# countercat_current.net
KiCad netlist of a schematic drawn in EAGLE
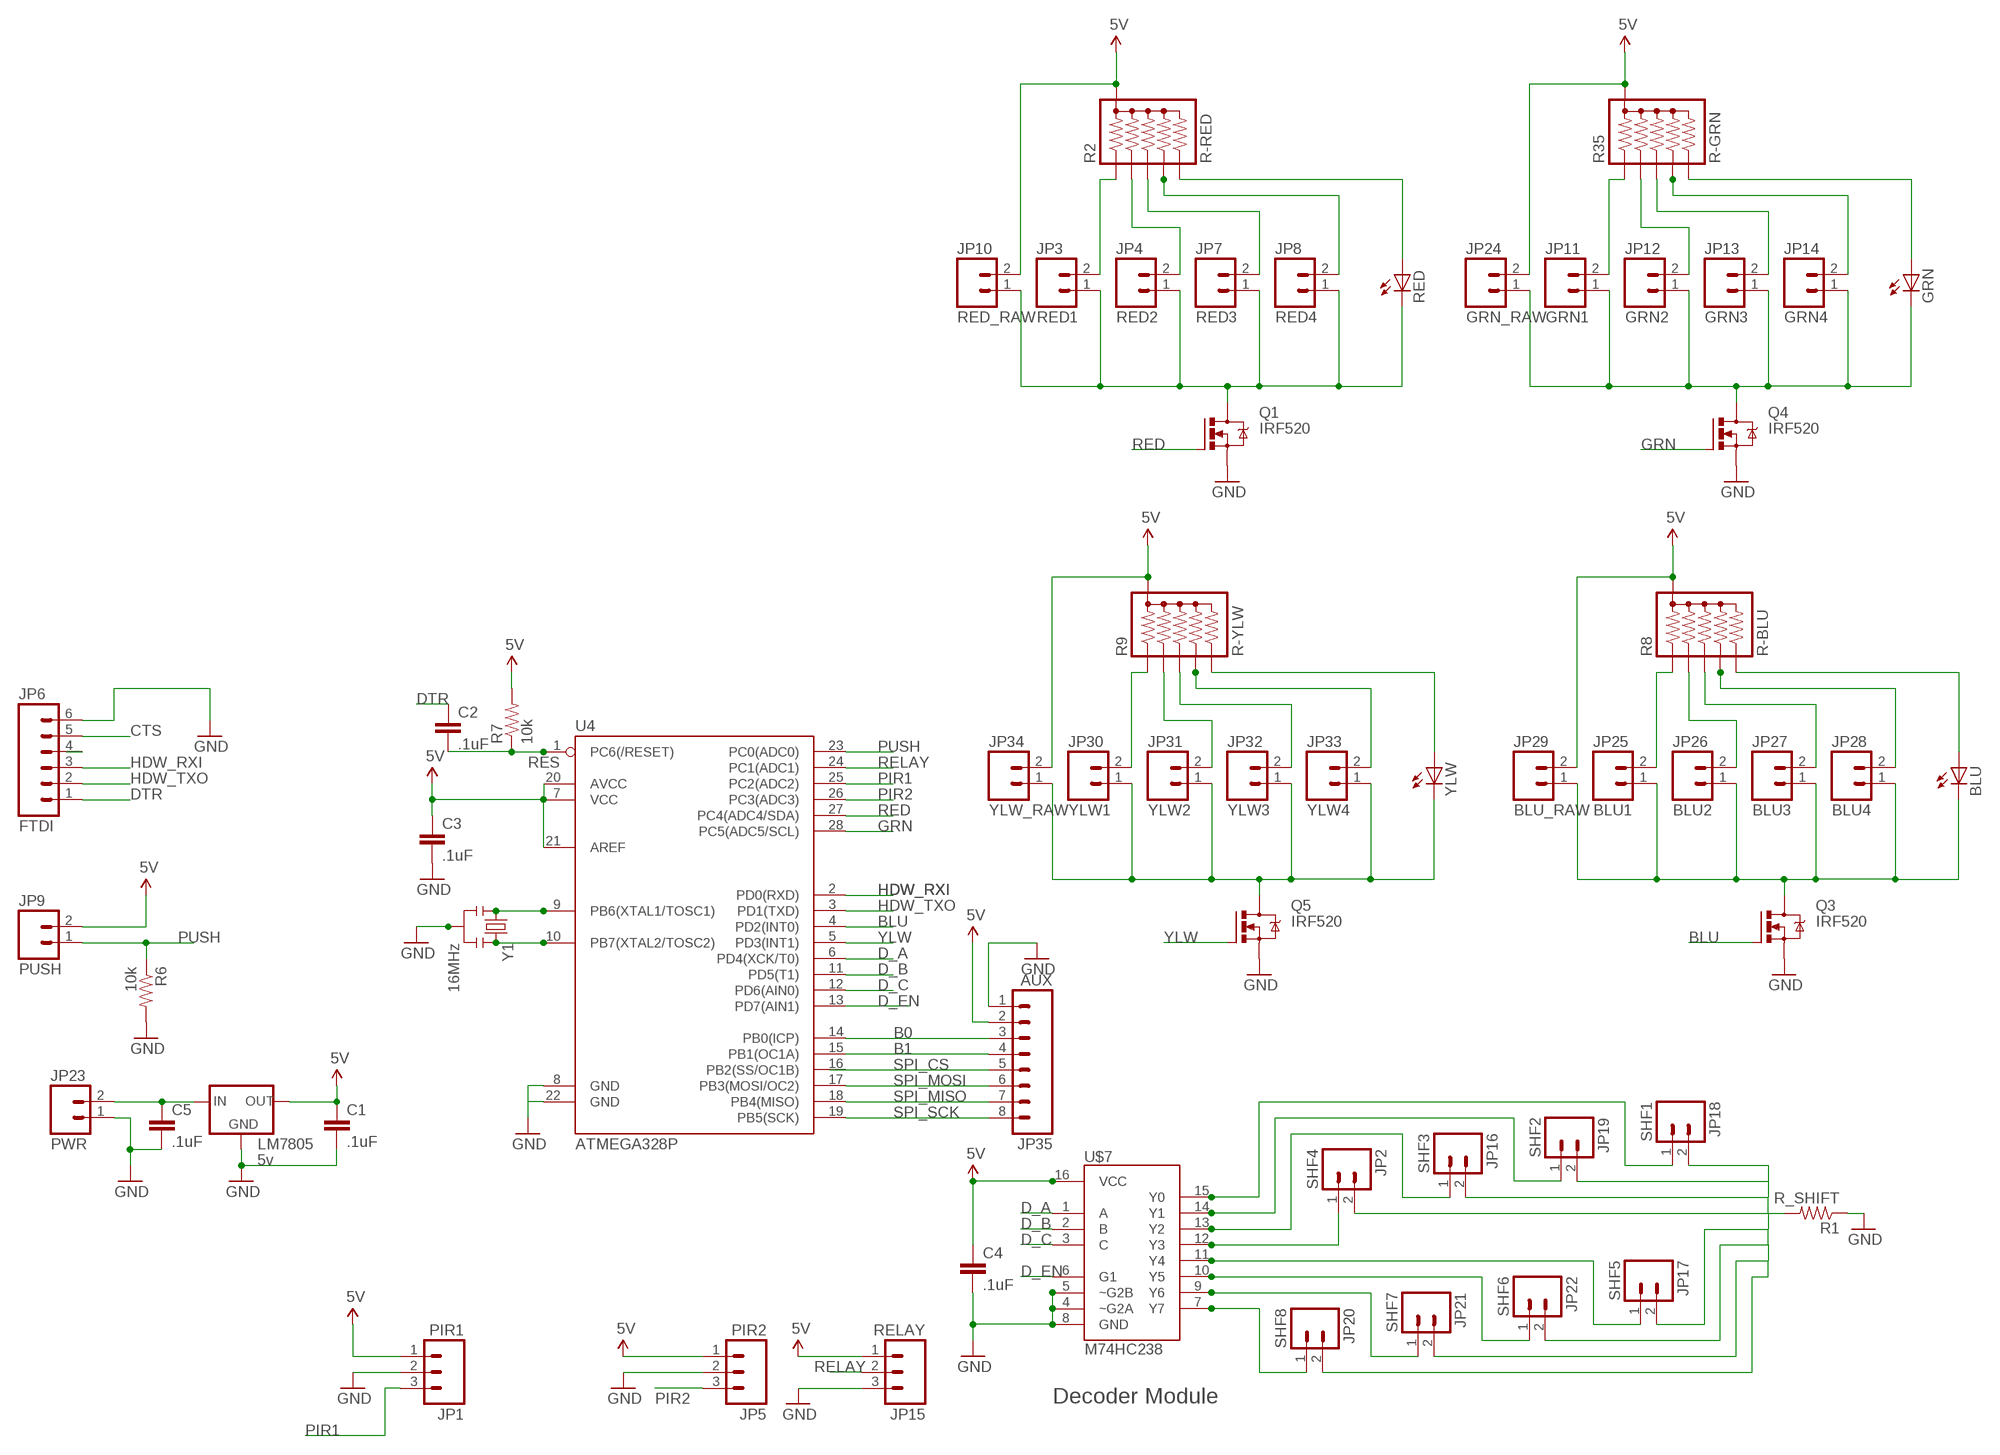
[diagram p0: schematic, sheet 1]

(export (version "E")
  (design (tool "Eeschema 10.0.6"))
  (components
    (comp (ref "BLU")
      (value "LED3MM")
      (footprint "eagle-import:LED3MM")
      (libsource (lib "eagle-import") (part "LED3MM"))
    )
    (comp (ref "C1")
      (value ".1uF")
      (footprint "eagle-import:CAP-PTH-SMALL2")
      (libsource (lib "eagle-import") (part "CAPPTH2"))
    )
    (comp (ref "C2")
      (value ".1uF")
      (footprint "eagle-import:CAP-PTH-SMALL2")
      (libsource (lib "eagle-import") (part "CAPPTH2"))
    )
    (comp (ref "C3")
      (value ".1uF")
      (footprint "eagle-import:CAP-PTH-SMALL2")
      (libsource (lib "eagle-import") (part "CAPPTH2"))
    )
    (comp (ref "C4")
      (value ".1uF")
      (footprint "eagle-import:CAP-PTH-SMALL2")
      (libsource (lib "eagle-import") (part "CAPPTH2"))
    )
    (comp (ref "C5")
      (value ".1uF")
      (footprint "eagle-import:CAP-PTH-SMALL2")
      (libsource (lib "eagle-import") (part "CAPPTH2"))
    )
    (comp (ref "GRN")
      (value "LED3MM")
      (footprint "eagle-import:LED3MM")
      (libsource (lib "eagle-import") (part "LED3MM"))
    )
    (comp (ref "JP1")
      (value "PIR1")
      (footprint "eagle-import:MOLEX-1X3")
      (libsource (lib "eagle-import") (part "M03POLAR"))
    )
    (comp (ref "JP2")
      (value "SHF4")
      (footprint "eagle-import:MOLEX-1X2")
      (libsource (lib "eagle-import") (part "M02POLAR"))
    )
    (comp (ref "JP3")
      (value "RED1")
      (footprint "eagle-import:MOLEX-1X2")
      (libsource (lib "eagle-import") (part "M02POLAR"))
    )
    (comp (ref "JP4")
      (value "RED2")
      (footprint "eagle-import:MOLEX-1X2")
      (libsource (lib "eagle-import") (part "M02POLAR"))
    )
    (comp (ref "JP5")
      (value "PIR2")
      (footprint "eagle-import:MOLEX-1X3")
      (libsource (lib "eagle-import") (part "M03POLAR"))
    )
    (comp (ref "JP6")
      (value "FTDI")
      (footprint "eagle-import:1X06_LOCK")
      (libsource (lib "eagle-import") (part "M06LOCK"))
    )
    (comp (ref "JP7")
      (value "RED3")
      (footprint "eagle-import:MOLEX-1X2")
      (libsource (lib "eagle-import") (part "M02POLAR"))
    )
    (comp (ref "JP8")
      (value "RED4")
      (footprint "eagle-import:MOLEX-1X2")
      (libsource (lib "eagle-import") (part "M02POLAR"))
    )
    (comp (ref "JP9")
      (value "PUSH")
      (footprint "eagle-import:MOLEX-1X2")
      (libsource (lib "eagle-import") (part "M02POLAR"))
    )
    (comp (ref "JP10")
      (value "RED_RAW")
      (footprint "eagle-import:MOLEX-1X2")
      (libsource (lib "eagle-import") (part "M02POLAR"))
    )
    (comp (ref "JP11")
      (value "GRN1")
      (footprint "eagle-import:MOLEX-1X2")
      (libsource (lib "eagle-import") (part "M02POLAR"))
    )
    (comp (ref "JP12")
      (value "GRN2")
      (footprint "eagle-import:MOLEX-1X2")
      (libsource (lib "eagle-import") (part "M02POLAR"))
    )
    (comp (ref "JP13")
      (value "GRN3")
      (footprint "eagle-import:MOLEX-1X2")
      (libsource (lib "eagle-import") (part "M02POLAR"))
    )
    (comp (ref "JP14")
      (value "GRN4")
      (footprint "eagle-import:MOLEX-1X2")
      (libsource (lib "eagle-import") (part "M02POLAR"))
    )
    (comp (ref "JP15")
      (value "RELAY")
      (footprint "eagle-import:MOLEX-1X3")
      (libsource (lib "eagle-import") (part "M03POLAR"))
    )
    (comp (ref "JP16")
      (value "SHF3")
      (footprint "eagle-import:MOLEX-1X2")
      (libsource (lib "eagle-import") (part "M02POLAR"))
    )
    (comp (ref "JP17")
      (value "SHF5")
      (footprint "eagle-import:MOLEX-1X2")
      (libsource (lib "eagle-import") (part "M02POLAR"))
    )
    (comp (ref "JP18")
      (value "SHF1")
      (footprint "eagle-import:MOLEX-1X2")
      (libsource (lib "eagle-import") (part "M02POLAR"))
    )
    (comp (ref "JP19")
      (value "SHF2")
      (footprint "eagle-import:MOLEX-1X2")
      (libsource (lib "eagle-import") (part "M02POLAR"))
    )
    (comp (ref "JP20")
      (value "SHF8")
      (footprint "eagle-import:MOLEX-1X2")
      (libsource (lib "eagle-import") (part "M02POLAR"))
    )
    (comp (ref "JP21")
      (value "SHF7")
      (footprint "eagle-import:MOLEX-1X2")
      (libsource (lib "eagle-import") (part "M02POLAR"))
    )
    (comp (ref "JP22")
      (value "SHF6")
      (footprint "eagle-import:MOLEX-1X2")
      (libsource (lib "eagle-import") (part "M02POLAR"))
    )
    (comp (ref "JP23")
      (value "PWR")
      (footprint "eagle-import:MOLEX-1X2")
      (libsource (lib "eagle-import") (part "M02POLAR"))
    )
    (comp (ref "JP24")
      (value "GRN_RAW")
      (footprint "eagle-import:MOLEX-1X2")
      (libsource (lib "eagle-import") (part "M02POLAR"))
    )
    (comp (ref "JP25")
      (value "BLU1")
      (footprint "eagle-import:MOLEX-1X2")
      (libsource (lib "eagle-import") (part "M02POLAR"))
    )
    (comp (ref "JP26")
      (value "BLU2")
      (footprint "eagle-import:MOLEX-1X2")
      (libsource (lib "eagle-import") (part "M02POLAR"))
    )
    (comp (ref "JP27")
      (value "BLU3")
      (footprint "eagle-import:MOLEX-1X2")
      (libsource (lib "eagle-import") (part "M02POLAR"))
    )
    (comp (ref "JP28")
      (value "BLU4")
      (footprint "eagle-import:MOLEX-1X2")
      (libsource (lib "eagle-import") (part "M02POLAR"))
    )
    (comp (ref "JP29")
      (value "BLU_RAW")
      (footprint "eagle-import:MOLEX-1X2")
      (libsource (lib "eagle-import") (part "M02POLAR"))
    )
    (comp (ref "JP30")
      (value "YLW1")
      (footprint "eagle-import:MOLEX-1X2")
      (libsource (lib "eagle-import") (part "M02POLAR"))
    )
    (comp (ref "JP31")
      (value "YLW2")
      (footprint "eagle-import:MOLEX-1X2")
      (libsource (lib "eagle-import") (part "M02POLAR"))
    )
    (comp (ref "JP32")
      (value "YLW3")
      (footprint "eagle-import:MOLEX-1X2")
      (libsource (lib "eagle-import") (part "M02POLAR"))
    )
    (comp (ref "JP33")
      (value "YLW4")
      (footprint "eagle-import:MOLEX-1X2")
      (libsource (lib "eagle-import") (part "M02POLAR"))
    )
    (comp (ref "JP34")
      (value "YLW_RAW")
      (footprint "eagle-import:MOLEX-1X2")
      (libsource (lib "eagle-import") (part "M02POLAR"))
    )
    (comp (ref "JP35")
      (value "AUX")
      (footprint "eagle-import:1X08_LOCK")
      (libsource (lib "eagle-import") (part "M08LOCK"))
    )
    (comp (ref "LM7805")
      (value "5v")
      (footprint "eagle-import:TO220-IGO")
      (libsource (lib "eagle-import") (part "V_REG_78XXSINK"))
    )
    (comp (ref "Q1")
      (value "IRF520")
      (footprint "eagle-import:TO220BV")
      (libsource (lib "eagle-import") (part "IRF520"))
    )
    (comp (ref "Q3")
      (value "IRF520")
      (footprint "eagle-import:TO220BV")
      (libsource (lib "eagle-import") (part "IRF520"))
    )
    (comp (ref "Q4")
      (value "IRF520")
      (footprint "eagle-import:TO220BV")
      (libsource (lib "eagle-import") (part "IRF520"))
    )
    (comp (ref "Q5")
      (value "IRF520")
      (footprint "eagle-import:TO220BV")
      (libsource (lib "eagle-import") (part "IRF520"))
    )
    (comp (ref "R1")
      (value "R_SHIFT")
      (footprint "eagle-import:AXIAL-0.4")
      (libsource (lib "eagle-import") (part "RESISTORPTH-1/4W"))
    )
    (comp (ref "R2")
      (value "R-RED")
      (footprint "eagle-import:RPACK-SIP-PTH-5")
      (libsource (lib "eagle-import") (part "RPACK-BUSSED-5-SIP-PTH-5"))
    )
    (comp (ref "R6")
      (value "10k")
      (footprint "eagle-import:AXIAL-0.4")
      (libsource (lib "eagle-import") (part "RESISTORPTH-1/4W"))
    )
    (comp (ref "R7")
      (value "10k")
      (footprint "eagle-import:AXIAL-0.4")
      (libsource (lib "eagle-import") (part "RESISTORPTH-1/4W"))
    )
    (comp (ref "R8")
      (value "R-BLU")
      (footprint "eagle-import:RPACK-SIP-PTH-5")
      (libsource (lib "eagle-import") (part "RPACK-BUSSED-5-SIP-PTH-5"))
    )
    (comp (ref "R9")
      (value "R-YLW")
      (footprint "eagle-import:RPACK-SIP-PTH-5")
      (libsource (lib "eagle-import") (part "RPACK-BUSSED-5-SIP-PTH-5"))
    )
    (comp (ref "R35")
      (value "R-GRN")
      (footprint "eagle-import:RPACK-SIP-PTH-5")
      (libsource (lib "eagle-import") (part "RPACK-BUSSED-5-SIP-PTH-5"))
    )
    (comp (ref "RED")
      (value "LED3MM")
      (footprint "eagle-import:LED3MM")
      (libsource (lib "eagle-import") (part "LED3MM"))
    )
    (comp (ref "U$7")
      (value "M74HC238")
      (footprint "eagle-import:DIL16")
      (libsource (lib "eagle-import") (part "M74HC238"))
    )
    (comp (ref "U4")
      (value "ATMEGA328P")
      (footprint "eagle-import:DIL28-3")
      (libsource (lib "eagle-import") (part "ATMEGA328P_PDIP"))
    )
    (comp (ref "Y1")
      (value "16MHz")
      (footprint "eagle-import:RESONATOR-PTH")
      (libsource (lib "eagle-import") (part "RESONATORPTH"))
    )
    (comp (ref "YLW")
      (value "LED3MM")
      (footprint "eagle-import:LED3MM")
      (libsource (lib "eagle-import") (part "LED3MM"))
    )
  )
  (nets
    (net (code "1") (name "/B0") (class "Default")
      (node (ref "JP35") (pin "3") (pinfunction "3_3") (pintype "passive"))
      (node (ref "U4") (pin "14") (pinfunction "PB0(ICP)_14") (pintype "bidirectional"))
    )
    (net (code "2") (name "/B1") (class "Default")
      (node (ref "JP35") (pin "4") (pinfunction "4_4") (pintype "passive"))
      (node (ref "U4") (pin "15") (pinfunction "PB1(OC1A)_15") (pintype "bidirectional"))
    )
    (net (code "3") (name "/BLU") (class "Default")
      (node (ref "Q3") (pin "G") (pinfunction "G_G") (pintype "passive"))
      (node (ref "U4") (pin "4") (pinfunction "PD2(INT0)_4") (pintype "bidirectional"))
    )
    (net (code "4") (name "/CTS") (class "Default")
      (node (ref "JP6") (pin "5") (pinfunction "5_5") (pintype "passive"))
    )
    (net (code "5") (name "/DTR") (class "Default")
      (node (ref "C2") (pin "1") (pinfunction "1_1") (pintype "passive"))
      (node (ref "JP6") (pin "1") (pinfunction "1_1") (pintype "passive"))
    )
    (net (code "6") (name "/D_A") (class "Default")
      (node (ref "U$7") (pin "1") (pinfunction "A_1") (pintype "bidirectional"))
      (node (ref "U4") (pin "6") (pinfunction "PD4(XCK/T0)_6") (pintype "bidirectional"))
    )
    (net (code "7") (name "/D_B") (class "Default")
      (node (ref "U$7") (pin "2") (pinfunction "B_2") (pintype "bidirectional"))
      (node (ref "U4") (pin "11") (pinfunction "PD5(T1)_11") (pintype "bidirectional"))
    )
    (net (code "8") (name "/D_C") (class "Default")
      (node (ref "U$7") (pin "3") (pinfunction "C_3") (pintype "bidirectional"))
      (node (ref "U4") (pin "12") (pinfunction "PD6(AIN0)_12") (pintype "bidirectional"))
    )
    (net (code "9") (name "/D_EN") (class "Default")
      (node (ref "U$7") (pin "6") (pinfunction "G1_6") (pintype "bidirectional"))
      (node (ref "U4") (pin "13") (pinfunction "PD7(AIN1)_13") (pintype "bidirectional"))
    )
    (net (code "10") (name "/GRN") (class "Default")
      (node (ref "Q4") (pin "G") (pinfunction "G_G") (pintype "passive"))
      (node (ref "U4") (pin "28") (pinfunction "PC5(ADC5/SCL)_28") (pintype "bidirectional"))
    )
    (net (code "11") (name "/HDW_RXI") (class "Default")
      (node (ref "JP6") (pin "3") (pinfunction "3_3") (pintype "passive"))
      (node (ref "U4") (pin "2") (pinfunction "PD0(RXD)_2") (pintype "bidirectional"))
    )
    (net (code "12") (name "/HDW_TXO") (class "Default")
      (node (ref "JP6") (pin "2") (pinfunction "2_2") (pintype "passive"))
      (node (ref "U4") (pin "3") (pinfunction "PD1(TXD)_3") (pintype "bidirectional"))
    )
    (net (code "13") (name "/PIR1") (class "Default")
      (node (ref "JP1") (pin "3") (pinfunction "3_3") (pintype "passive"))
      (node (ref "U4") (pin "25") (pinfunction "PC2(ADC2)_25") (pintype "bidirectional"))
    )
    (net (code "14") (name "/PIR2") (class "Default")
      (node (ref "JP5") (pin "3") (pinfunction "3_3") (pintype "passive"))
      (node (ref "U4") (pin "26") (pinfunction "PC3(ADC3)_26") (pintype "bidirectional"))
    )
    (net (code "15") (name "/PUSH") (class "Default")
      (node (ref "JP9") (pin "1") (pinfunction "1_1") (pintype "passive"))
      (node (ref "R6") (pin "P$1") (pinfunction "1_P$1") (pintype "passive"))
      (node (ref "U4") (pin "23") (pinfunction "PC0(ADC0)_23") (pintype "bidirectional"))
    )
    (net (code "16") (name "/RED") (class "Default")
      (node (ref "Q1") (pin "G") (pinfunction "G_G") (pintype "passive"))
      (node (ref "U4") (pin "27") (pinfunction "PC4(ADC4/SDA)_27") (pintype "bidirectional"))
    )
    (net (code "17") (name "/RELAY") (class "Default")
      (node (ref "JP15") (pin "2") (pinfunction "2_2") (pintype "passive"))
      (node (ref "U4") (pin "24") (pinfunction "PC1(ADC1)_24") (pintype "bidirectional"))
    )
    (net (code "18") (name "/RES") (class "Default")
      (node (ref "C2") (pin "2") (pinfunction "2_2") (pintype "passive"))
      (node (ref "R7") (pin "P$1") (pinfunction "1_P$1") (pintype "passive"))
      (node (ref "U4") (pin "1") (pinfunction "PC6(/RESET)_1") (pintype "bidirectional"))
    )
    (net (code "19") (name "/SPI_CS") (class "Default")
      (node (ref "JP35") (pin "5") (pinfunction "5_5") (pintype "passive"))
      (node (ref "U4") (pin "16") (pinfunction "PB2(SS/OC1B)_16") (pintype "bidirectional"))
    )
    (net (code "20") (name "/SPI_MISO") (class "Default")
      (node (ref "JP35") (pin "7") (pinfunction "7_7") (pintype "passive"))
      (node (ref "U4") (pin "18") (pinfunction "PB4(MISO)_18") (pintype "bidirectional"))
    )
    (net (code "21") (name "/SPI_MOSI") (class "Default")
      (node (ref "JP35") (pin "6") (pinfunction "6_6") (pintype "passive"))
      (node (ref "U4") (pin "17") (pinfunction "PB3(MOSI/OC2)_17") (pintype "bidirectional"))
    )
    (net (code "22") (name "/SPI_SCK") (class "Default")
      (node (ref "JP35") (pin "8") (pinfunction "8_8") (pintype "passive"))
      (node (ref "U4") (pin "19") (pinfunction "PB5(SCK)_19") (pintype "bidirectional"))
    )
    (net (code "23") (name "/YLW") (class "Default")
      (node (ref "Q5") (pin "G") (pinfunction "G_G") (pintype "passive"))
      (node (ref "U4") (pin "5") (pinfunction "PD3(INT1)_5") (pintype "bidirectional"))
    )
    (net (code "24") (name "5V") (class "Default")
      (node (ref "C1") (pin "1") (pinfunction "1_1") (pintype "passive"))
      (node (ref "C3") (pin "1") (pinfunction "1_1") (pintype "passive"))
      (node (ref "C4") (pin "1") (pinfunction "1_1") (pintype "passive"))
      (node (ref "JP1") (pin "1") (pinfunction "1_1") (pintype "passive"))
      (node (ref "JP10") (pin "2") (pinfunction "2_2") (pintype "passive"))
      (node (ref "JP15") (pin "1") (pinfunction "1_1") (pintype "passive"))
      (node (ref "JP24") (pin "2") (pinfunction "2_2") (pintype "passive"))
      (node (ref "JP29") (pin "2") (pinfunction "2_2") (pintype "passive"))
      (node (ref "JP34") (pin "2") (pinfunction "2_2") (pintype "passive"))
      (node (ref "JP35") (pin "2") (pinfunction "2_2") (pintype "passive"))
      (node (ref "JP5") (pin "1") (pinfunction "1_1") (pintype "passive"))
      (node (ref "JP9") (pin "2") (pinfunction "2_2") (pintype "passive"))
      (node (ref "LM7805") (pin "OUT") (pinfunction "OUT_OUT") (pintype "output"))
      (node (ref "R2") (pin "P$1") (pinfunction "1_P$1") (pintype "passive"))
      (node (ref "R35") (pin "P$1") (pinfunction "1_P$1") (pintype "passive"))
      (node (ref "R7") (pin "P$2") (pinfunction "2_P$2") (pintype "passive"))
      (node (ref "R8") (pin "P$1") (pinfunction "1_P$1") (pintype "passive"))
      (node (ref "R9") (pin "P$1") (pinfunction "1_P$1") (pintype "passive"))
      (node (ref "U$7") (pin "16") (pinfunction "VCC_16") (pintype "bidirectional"))
      (node (ref "U4") (pin "20") (pinfunction "AVCC_20") (pintype "bidirectional"))
      (node (ref "U4") (pin "21") (pinfunction "AREF_21") (pintype "bidirectional"))
      (node (ref "U4") (pin "7") (pinfunction "VCC_7") (pintype "bidirectional"))
    )
    (net (code "25") (name "GND") (class "Default")
      (node (ref "C1") (pin "2") (pinfunction "2_2") (pintype "passive"))
      (node (ref "C3") (pin "2") (pinfunction "2_2") (pintype "passive"))
      (node (ref "C4") (pin "2") (pinfunction "2_2") (pintype "passive"))
      (node (ref "C5") (pin "2") (pinfunction "2_2") (pintype "passive"))
      (node (ref "JP1") (pin "2") (pinfunction "2_2") (pintype "passive"))
      (node (ref "JP15") (pin "3") (pinfunction "3_3") (pintype "passive"))
      (node (ref "JP23") (pin "1") (pinfunction "1_1") (pintype "passive"))
      (node (ref "JP35") (pin "1") (pinfunction "1_1") (pintype "passive"))
      (node (ref "JP5") (pin "2") (pinfunction "2_2") (pintype "passive"))
      (node (ref "JP6") (pin "6") (pinfunction "6_6") (pintype "passive"))
      (node (ref "LM7805") (pin "GND") (pinfunction "GND_GND") (pintype "input"))
      (node (ref "Q1") (pin "S") (pinfunction "S_S") (pintype "passive"))
      (node (ref "Q3") (pin "S") (pinfunction "S_S") (pintype "passive"))
      (node (ref "Q4") (pin "S") (pinfunction "S_S") (pintype "passive"))
      (node (ref "Q5") (pin "S") (pinfunction "S_S") (pintype "passive"))
      (node (ref "R1") (pin "P$1") (pinfunction "1_P$1") (pintype "passive"))
      (node (ref "R6") (pin "P$2") (pinfunction "2_P$2") (pintype "passive"))
      (node (ref "U$7") (pin "4") (pinfunction "~{G2A}_4") (pintype "bidirectional"))
      (node (ref "U$7") (pin "5") (pinfunction "~{G2B}_5") (pintype "bidirectional"))
      (node (ref "U$7") (pin "8") (pinfunction "GND_8") (pintype "bidirectional"))
      (node (ref "U4") (pin "22") (pinfunction "GND_22") (pintype "bidirectional"))
      (node (ref "U4") (pin "8") (pinfunction "GND_8") (pintype "bidirectional"))
      (node (ref "Y1") (pin "2") (pinfunction "2_2") (pintype "passive"))
    )
    (net (code "26") (name "Net-(BLU-C)") (class "Default")
      (node (ref "BLU") (pin "K") (pinfunction "C_K") (pintype "passive"))
      (node (ref "JP25") (pin "1") (pinfunction "1_1") (pintype "passive"))
      (node (ref "JP26") (pin "1") (pinfunction "1_1") (pintype "passive"))
      (node (ref "JP27") (pin "1") (pinfunction "1_1") (pintype "passive"))
      (node (ref "JP28") (pin "1") (pinfunction "1_1") (pintype "passive"))
      (node (ref "JP29") (pin "1") (pinfunction "1_1") (pintype "passive"))
      (node (ref "Q3") (pin "D") (pinfunction "D_D") (pintype "passive"))
    )
    (net (code "27") (name "Net-(C5-Pad1)") (class "Default")
      (node (ref "C5") (pin "1") (pinfunction "1_1") (pintype "passive"))
      (node (ref "JP23") (pin "2") (pinfunction "2_2") (pintype "passive"))
      (node (ref "LM7805") (pin "IN") (pinfunction "IN_IN") (pintype "input"))
    )
    (net (code "28") (name "Net-(GRN-C)") (class "Default")
      (node (ref "GRN") (pin "K") (pinfunction "C_K") (pintype "passive"))
      (node (ref "JP11") (pin "1") (pinfunction "1_1") (pintype "passive"))
      (node (ref "JP12") (pin "1") (pinfunction "1_1") (pintype "passive"))
      (node (ref "JP13") (pin "1") (pinfunction "1_1") (pintype "passive"))
      (node (ref "JP14") (pin "1") (pinfunction "1_1") (pintype "passive"))
      (node (ref "JP24") (pin "1") (pinfunction "1_1") (pintype "passive"))
      (node (ref "Q4") (pin "D") (pinfunction "D_D") (pintype "passive"))
    )
    (net (code "29") (name "Net-(R1-2)") (class "Default")
      (node (ref "JP16") (pin "2") (pinfunction "2_2") (pintype "passive"))
      (node (ref "JP17") (pin "2") (pinfunction "2_2") (pintype "passive"))
      (node (ref "JP18") (pin "2") (pinfunction "2_2") (pintype "passive"))
      (node (ref "JP19") (pin "2") (pinfunction "2_2") (pintype "passive"))
      (node (ref "JP2") (pin "2") (pinfunction "2_2") (pintype "passive"))
      (node (ref "JP20") (pin "2") (pinfunction "2_2") (pintype "passive"))
      (node (ref "JP21") (pin "2") (pinfunction "2_2") (pintype "passive"))
      (node (ref "JP22") (pin "2") (pinfunction "2_2") (pintype "passive"))
      (node (ref "R1") (pin "P$2") (pinfunction "2_P$2") (pintype "passive"))
    )
    (net (code "30") (name "Net-(R2-2)") (class "Default")
      (node (ref "JP3") (pin "2") (pinfunction "2_2") (pintype "passive"))
      (node (ref "R2") (pin "P$2") (pinfunction "2_P$2") (pintype "passive"))
    )
    (net (code "31") (name "Net-(R2-3)") (class "Default")
      (node (ref "JP4") (pin "2") (pinfunction "2_2") (pintype "passive"))
      (node (ref "R2") (pin "P$3") (pinfunction "3_P$3") (pintype "passive"))
    )
    (net (code "32") (name "Net-(R2-4)") (class "Default")
      (node (ref "JP7") (pin "2") (pinfunction "2_2") (pintype "passive"))
      (node (ref "R2") (pin "P$4") (pinfunction "4_P$4") (pintype "passive"))
    )
    (net (code "33") (name "Net-(R2-5)") (class "Default")
      (node (ref "JP8") (pin "2") (pinfunction "2_2") (pintype "passive"))
      (node (ref "R2") (pin "P$5") (pinfunction "5_P$5") (pintype "passive"))
    )
    (net (code "34") (name "Net-(R2-6)") (class "Default")
      (node (ref "R2") (pin "P$6") (pinfunction "6_P$6") (pintype "passive"))
      (node (ref "RED") (pin "A") (pinfunction "A_A") (pintype "passive"))
    )
    (net (code "35") (name "Net-(R8-2)") (class "Default")
      (node (ref "JP25") (pin "2") (pinfunction "2_2") (pintype "passive"))
      (node (ref "R8") (pin "P$2") (pinfunction "2_P$2") (pintype "passive"))
    )
    (net (code "36") (name "Net-(R8-3)") (class "Default")
      (node (ref "JP26") (pin "2") (pinfunction "2_2") (pintype "passive"))
      (node (ref "R8") (pin "P$3") (pinfunction "3_P$3") (pintype "passive"))
    )
    (net (code "37") (name "Net-(R8-4)") (class "Default")
      (node (ref "JP27") (pin "2") (pinfunction "2_2") (pintype "passive"))
      (node (ref "R8") (pin "P$4") (pinfunction "4_P$4") (pintype "passive"))
    )
    (net (code "38") (name "Net-(R8-5)") (class "Default")
      (node (ref "JP28") (pin "2") (pinfunction "2_2") (pintype "passive"))
      (node (ref "R8") (pin "P$5") (pinfunction "5_P$5") (pintype "passive"))
    )
    (net (code "39") (name "Net-(R8-6)") (class "Default")
      (node (ref "BLU") (pin "A") (pinfunction "A_A") (pintype "passive"))
      (node (ref "R8") (pin "P$6") (pinfunction "6_P$6") (pintype "passive"))
    )
    (net (code "40") (name "Net-(R9-2)") (class "Default")
      (node (ref "JP30") (pin "2") (pinfunction "2_2") (pintype "passive"))
      (node (ref "R9") (pin "P$2") (pinfunction "2_P$2") (pintype "passive"))
    )
    (net (code "41") (name "Net-(R9-3)") (class "Default")
      (node (ref "JP31") (pin "2") (pinfunction "2_2") (pintype "passive"))
      (node (ref "R9") (pin "P$3") (pinfunction "3_P$3") (pintype "passive"))
    )
    (net (code "42") (name "Net-(R9-4)") (class "Default")
      (node (ref "JP32") (pin "2") (pinfunction "2_2") (pintype "passive"))
      (node (ref "R9") (pin "P$4") (pinfunction "4_P$4") (pintype "passive"))
    )
    (net (code "43") (name "Net-(R9-5)") (class "Default")
      (node (ref "JP33") (pin "2") (pinfunction "2_2") (pintype "passive"))
      (node (ref "R9") (pin "P$5") (pinfunction "5_P$5") (pintype "passive"))
    )
    (net (code "44") (name "Net-(R9-6)") (class "Default")
      (node (ref "R9") (pin "P$6") (pinfunction "6_P$6") (pintype "passive"))
      (node (ref "YLW") (pin "A") (pinfunction "A_A") (pintype "passive"))
    )
    (net (code "45") (name "Net-(R35-2)") (class "Default")
      (node (ref "JP11") (pin "2") (pinfunction "2_2") (pintype "passive"))
      (node (ref "R35") (pin "P$2") (pinfunction "2_P$2") (pintype "passive"))
    )
    (net (code "46") (name "Net-(R35-3)") (class "Default")
      (node (ref "JP12") (pin "2") (pinfunction "2_2") (pintype "passive"))
      (node (ref "R35") (pin "P$3") (pinfunction "3_P$3") (pintype "passive"))
    )
    (net (code "47") (name "Net-(R35-4)") (class "Default")
      (node (ref "JP13") (pin "2") (pinfunction "2_2") (pintype "passive"))
      (node (ref "R35") (pin "P$4") (pinfunction "4_P$4") (pintype "passive"))
    )
    (net (code "48") (name "Net-(R35-5)") (class "Default")
      (node (ref "JP14") (pin "2") (pinfunction "2_2") (pintype "passive"))
      (node (ref "R35") (pin "P$5") (pinfunction "5_P$5") (pintype "passive"))
    )
    (net (code "49") (name "Net-(R35-6)") (class "Default")
      (node (ref "GRN") (pin "A") (pinfunction "A_A") (pintype "passive"))
      (node (ref "R35") (pin "P$6") (pinfunction "6_P$6") (pintype "passive"))
    )
    (net (code "50") (name "Net-(RED-C)") (class "Default")
      (node (ref "JP10") (pin "1") (pinfunction "1_1") (pintype "passive"))
      (node (ref "JP3") (pin "1") (pinfunction "1_1") (pintype "passive"))
      (node (ref "JP4") (pin "1") (pinfunction "1_1") (pintype "passive"))
      (node (ref "JP7") (pin "1") (pinfunction "1_1") (pintype "passive"))
      (node (ref "JP8") (pin "1") (pinfunction "1_1") (pintype "passive"))
      (node (ref "Q1") (pin "D") (pinfunction "D_D") (pintype "passive"))
      (node (ref "RED") (pin "K") (pinfunction "C_K") (pintype "passive"))
    )
    (net (code "51") (name "Net-(U$7-Y0)") (class "Default")
      (node (ref "JP18") (pin "1") (pinfunction "1_1") (pintype "passive"))
      (node (ref "U$7") (pin "15") (pinfunction "Y0_15") (pintype "bidirectional"))
    )
    (net (code "52") (name "Net-(U$7-Y1)") (class "Default")
      (node (ref "JP19") (pin "1") (pinfunction "1_1") (pintype "passive"))
      (node (ref "U$7") (pin "14") (pinfunction "Y1_14") (pintype "bidirectional"))
    )
    (net (code "53") (name "Net-(U$7-Y2)") (class "Default")
      (node (ref "JP16") (pin "1") (pinfunction "1_1") (pintype "passive"))
      (node (ref "U$7") (pin "13") (pinfunction "Y2_13") (pintype "bidirectional"))
    )
    (net (code "54") (name "Net-(U$7-Y3)") (class "Default")
      (node (ref "JP2") (pin "1") (pinfunction "1_1") (pintype "passive"))
      (node (ref "U$7") (pin "12") (pinfunction "Y3_12") (pintype "bidirectional"))
    )
    (net (code "55") (name "Net-(U$7-Y4)") (class "Default")
      (node (ref "JP17") (pin "1") (pinfunction "1_1") (pintype "passive"))
      (node (ref "U$7") (pin "11") (pinfunction "Y4_11") (pintype "bidirectional"))
    )
    (net (code "56") (name "Net-(U$7-Y5)") (class "Default")
      (node (ref "JP22") (pin "1") (pinfunction "1_1") (pintype "passive"))
      (node (ref "U$7") (pin "10") (pinfunction "Y5_10") (pintype "bidirectional"))
    )
    (net (code "57") (name "Net-(U$7-Y6)") (class "Default")
      (node (ref "JP21") (pin "1") (pinfunction "1_1") (pintype "passive"))
      (node (ref "U$7") (pin "9") (pinfunction "Y6_9") (pintype "bidirectional"))
    )
    (net (code "58") (name "Net-(U$7-Y7)") (class "Default")
      (node (ref "JP20") (pin "1") (pinfunction "1_1") (pintype "passive"))
      (node (ref "U$7") (pin "7") (pinfunction "Y7_7") (pintype "bidirectional"))
    )
    (net (code "59") (name "Net-(U4-PB6(XTAL1{slash}TOSC1))") (class "Default")
      (node (ref "U4") (pin "9") (pinfunction "PB6(XTAL1/TOSC1)_9") (pintype "bidirectional"))
      (node (ref "Y1") (pin "1") (pinfunction "1_1") (pintype "passive"))
    )
    (net (code "60") (name "Net-(U4-PB7(XTAL2{slash}TOSC2))") (class "Default")
      (node (ref "U4") (pin "10") (pinfunction "PB7(XTAL2/TOSC2)_10") (pintype "bidirectional"))
      (node (ref "Y1") (pin "3") (pinfunction "3_3") (pintype "passive"))
    )
    (net (code "61") (name "Net-(YLW-C)") (class "Default")
      (node (ref "JP30") (pin "1") (pinfunction "1_1") (pintype "passive"))
      (node (ref "JP31") (pin "1") (pinfunction "1_1") (pintype "passive"))
      (node (ref "JP32") (pin "1") (pinfunction "1_1") (pintype "passive"))
      (node (ref "JP33") (pin "1") (pinfunction "1_1") (pintype "passive"))
      (node (ref "JP34") (pin "1") (pinfunction "1_1") (pintype "passive"))
      (node (ref "Q5") (pin "D") (pinfunction "D_D") (pintype "passive"))
      (node (ref "YLW") (pin "K") (pinfunction "C_K") (pintype "passive"))
    )
    (net (code "62") (name "unconnected-(JP6-Pad4)") (class "Default")
      (node (ref "JP6") (pin "4") (pinfunction "4_4") (pintype "passive"))
    )
  )
)
